# GPS.net
KiCad netlist of a schematic drawn in Altium Designer
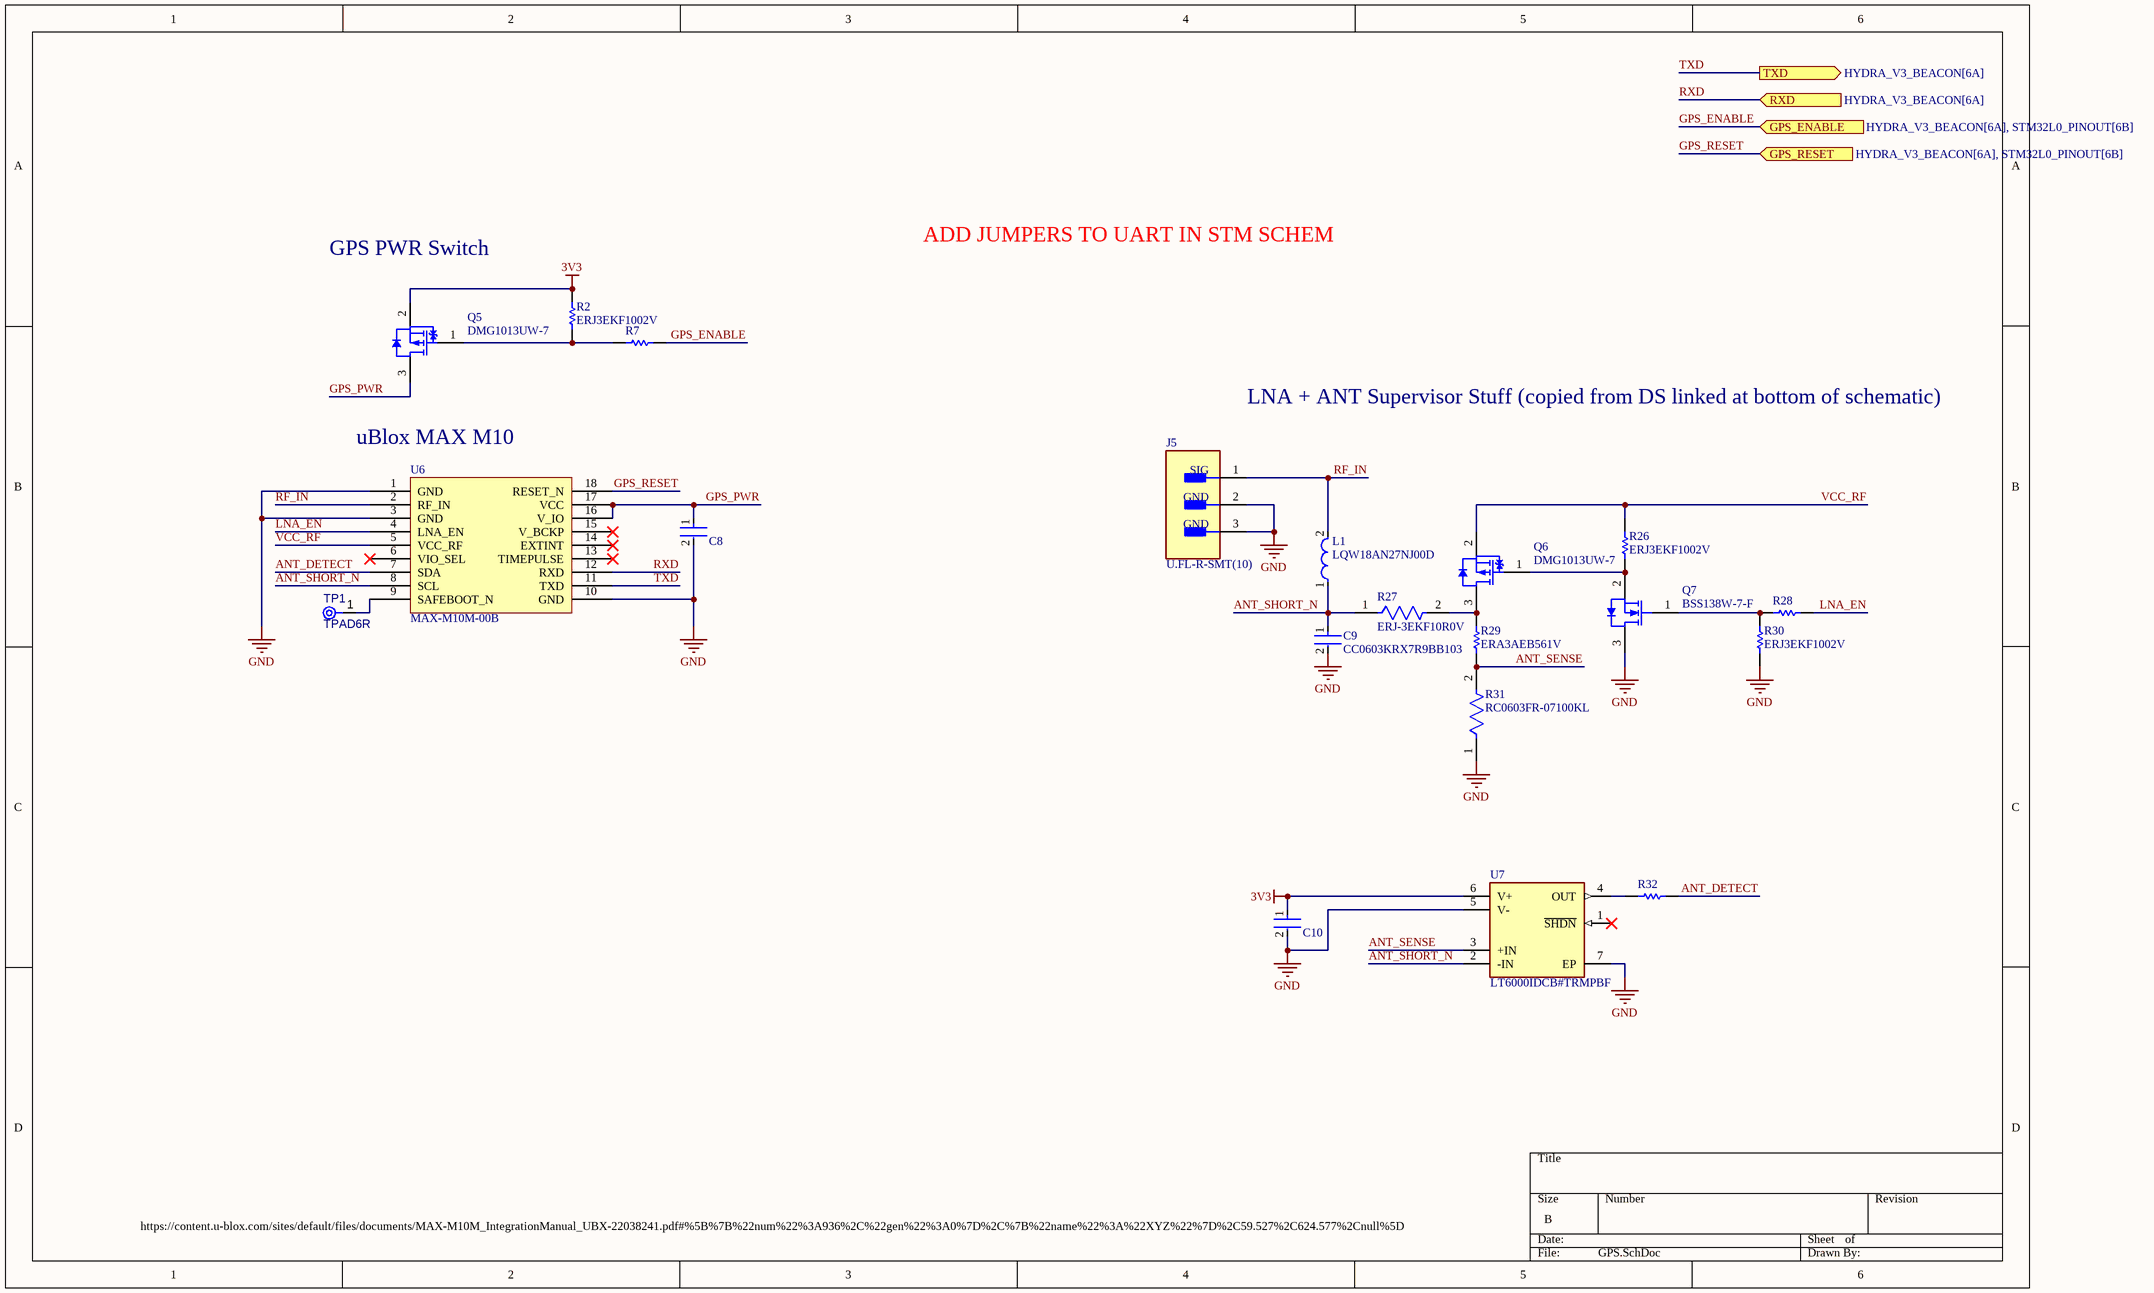
[diagram p0: GPS.SchDoc]

(export (version "E")
  (design (tool "Eeschema 10.0.6"))
  (components
    (comp (ref "C8")
      (value "C0402C104K8PACTU")
      (footprint "FP-C0402-BB-MFG")
      (description "CAP CER 0.1UF 10V X5R 0402")
      (fields (field (name "MANUFACTURER") "Kemet") (field (name "TOLERANCE") "0.1"))
      (libsource (lib "Altium Content Vault") (part "b4654b650e69147ec39a6b967a45e02"))
    )
    (comp (ref "C9")
      (value "CC0603KRX7R9BB103")
      (footprint "FP-CC0603-DA-MFG")
      (description "CAP CER 10000PF 50V X7R 0603")
      (fields (field (name "TOLERANCE") "0.1") (field (name "MANUFACTURER") "YAGEO"))
      (libsource (lib "Altium Content Vault") (part "11868f565c42a9108669ba33697ecf6"))
    )
    (comp (ref "C10")
      (value "C0402C104K8PACTU")
      (footprint "FP-C0402-BB-MFG")
      (description "CAP CER 0.1UF 10V X5R 0402")
      (fields (field (name "MANUFACTURER") "Kemet") (field (name "TOLERANCE") "0.1"))
      (libsource (lib "Altium Content Vault") (part "b4654b650e69147ec39a6b967a45e02"))
    )
    (comp (ref "J5")
      (value "U.FL-R-SMT(10)")
      (footprint "FP-U_FL-R-SMT_10-MFG")
      (description "CONN U.FL RCPT STR 50 OHM SMD")
      (libsource (lib "Altium Content Vault") (part "eef6fde44c591823e8076210edfe12f"))
    )
    (comp (ref "L1")
      (value "LQW18AN27NJ00D")
      (footprint "FP-LQW18AN_00-MFG")
      (description "Wire Wound RF Inductor 27nH ±5% 440mA 0.21Ω 0603 (1608)")
      (fields (field (name "TOLERANCE") "5%"))
      (libsource (lib "Altium Content Vault") (part "725321dda6339637d4d059423bc1c3c"))
    )
    (comp (ref "Q5")
      (value "DMG1013UW-7")
      (footprint "DIOD-SOT323-3_V")
      (fields (field (name "MANUFACTURER") "Diodes Inc"))
      (libsource (lib "Altium Content Vault") (part "PEMOS-GSD-3_C"))
    )
    (comp (ref "Q6")
      (value "DMG1013UW-7")
      (footprint "DIOD-SOT323-3_V")
      (fields (field (name "MANUFACTURER") "Diodes Inc"))
      (libsource (lib "Altium Content Vault") (part "PEMOS-GSD-3_C"))
    )
    (comp (ref "Q7")
      (value "BSS138W-7-F")
      (footprint "DIOD-SOT323-3_V")
      (fields (field (name "MANUFACTURER") "DiodesIncorporated"))
      (libsource (lib "Altium Content Vault") (part "NEMOS-GSD-3"))
    )
    (comp (ref "R2")
      (value "ERJ3EKF1002V")
      (footprint "RESC1609X55X30LL15T15")
      (description "Chip Resistor, 10 KOhm, +/- 1%, 0.1 W, -55 to 155 degC, 0603 (1608 Metric), RoHS, Tape and Reel")
      (fields (field (name "TOLERANCE") "1%") (field (name "MANUFACTURER") "Panasonic"))
      (libsource (lib "Altium Content Vault") (part "RES-2"))
    )
    (comp (ref "R7")
      (value "ERJ-3EKF1001V")
      (footprint "RESC1608X55X30LL15T15")
      (fields (field (name "MANUFACTURER") "Panasonic"))
      (libsource (lib "Altium Content Vault") (part "RES"))
    )
    (comp (ref "R26")
      (value "ERJ3EKF1002V")
      (footprint "RESC1609X55X30LL15T15")
      (description "Chip Resistor, 10 KOhm, +/- 1%, 0.1 W, -55 to 155 degC, 0603 (1608 Metric), RoHS, Tape and Reel")
      (fields (field (name "TOLERANCE") "1%") (field (name "MANUFACTURER") "Panasonic"))
      (libsource (lib "Altium Content Vault") (part "RES-2"))
    )
    (comp (ref "R27")
      (value "ERJ-3EKF10R0V")
      (footprint "FP-ERJ3EK-MFG")
      (description "RES SMD 10 OHM 1% 1/10W 0603")
      (fields
        (field (name "OCTOPART") "https://octopart.com/erj-3ekf10r0v-panasonic-55403649")
        (field (name "MANUFACTURER") "Panasonic")
      )
      (libsource (lib "Altium Content Vault") (part "1029c3af85768c4190bb7ad29bc67b5"))
    )
    (comp (ref "R28")
      (value "ERJ-3EKF1001V")
      (footprint "RESC1608X55X30LL15T15")
      (fields (field (name "MANUFACTURER") "Panasonic"))
      (libsource (lib "Altium Content Vault") (part "RES"))
    )
    (comp (ref "R29")
      (value "ERA3AEB561V")
      (footprint "RESC1608X55X30LL20T20")
      (fields (field (name "MANUFACTURER") "Panasonic"))
      (libsource (lib "Altium Content Vault") (part "RES"))
    )
    (comp (ref "R30")
      (value "ERJ3EKF1002V")
      (footprint "RESC1609X55X30LL15T15")
      (description "Chip Resistor, 10 KOhm, +/- 1%, 0.1 W, -55 to 155 degC, 0603 (1608 Metric), RoHS, Tape and Reel")
      (fields (field (name "TOLERANCE") "1%") (field (name "MANUFACTURER") "Panasonic"))
      (libsource (lib "Altium Content Vault") (part "RES-2"))
    )
    (comp (ref "R31")
      (value "RC0603FR-07100KL")
      (footprint "FP-RC0603-0_55-MFG")
      (description "RES SMD 100K OHM 1% 1/10W 0603")
      (fields (field (name "TOLERANCE") "1%"))
      (libsource (lib "Altium Content Vault") (part "1029c3af85768c4190bb7ad29bc67b5"))
    )
    (comp (ref "R32")
      (value "ERJ-3EKF1001V")
      (footprint "RESC1608X55X30LL15T15")
      (fields (field (name "MANUFACTURER") "Panasonic"))
      (libsource (lib "Altium Content Vault") (part "RES"))
    )
    (comp (ref "TP1")
      (value "TPAD6R")
      (footprint "TP06R")
      (description "0.6mm round")
      (libsource (lib "uORocketry Hardware") (part "CMP-001-0001-4"))
    )
    (comp (ref "U6")
      (value "MAX-M10M-00B")
      (footprint "CAC-110P1035X969-18N")
      (description "Gnss Lcc Rx Mod, Rom, Crystal")
      (libsource (lib "uORocketry Hardware") (part "MAX-M10M-00B"))
    )
    (comp (ref "U7")
      (value "LT6000IDCB#TRMPBF")
      (footprint "FP-DCB-6-05-08-1715-MFG")
      (description "IC OPAMP GP 1 CIRCUIT 6DFN")
      (libsource (lib "Altium Content Vault") (part "33bb285994f2e703f79bf9d86341a8a"))
    )
  )
  (nets
    (net (code "1") (name "/ANT_DETECT") (class "Default")
      (node (ref "R32") (pin "1") (pinfunction "1_1") (pintype "passive"))
      (node (ref "U6") (pin "7") (pinfunction "SDA_7") (pintype "passive"))
    )
    (net (code "2") (name "/ANT_SENSE") (class "Default")
      (node (ref "R29") (pin "1") (pinfunction "1_1") (pintype "passive"))
      (node (ref "R31") (pin "2") (pinfunction "2_2") (pintype "passive"))
      (node (ref "U7") (pin "3") (pinfunction "+IN_3") (pintype "tri_state"))
    )
    (net (code "3") (name "/ANT_SHORT_N") (class "Default")
      (node (ref "C9") (pin "1") (pinfunction "1_1") (pintype "passive"))
      (node (ref "L1") (pin "1") (pinfunction "1_1") (pintype "passive"))
      (node (ref "R27") (pin "1") (pinfunction "1_1") (pintype "passive"))
      (node (ref "U6") (pin "8") (pinfunction "SCL_8") (pintype "passive"))
      (node (ref "U7") (pin "2") (pinfunction "-IN_2") (pintype "tri_state"))
    )
    (net (code "4") (name "/GPS_ENABLE") (class "Default")
      (node (ref "R7") (pin "1") (pinfunction "1_1") (pintype "passive"))
    )
    (net (code "5") (name "/GPS_PWR") (class "Default")
      (node (ref "C8") (pin "1") (pinfunction "1_1") (pintype "passive"))
      (node (ref "Q5") (pin "3") (pinfunction "D_3") (pintype "passive"))
      (node (ref "U6") (pin "16") (pinfunction "V_IO_16") (pintype "passive"))
      (node (ref "U6") (pin "17") (pinfunction "VCC_17") (pintype "passive"))
    )
    (net (code "6") (name "/GPS_RESET") (class "Default")
      (node (ref "U6") (pin "18") (pinfunction "RESET_N_18") (pintype "passive"))
    )
    (net (code "7") (name "/LNA_EN") (class "Default")
      (node (ref "R28") (pin "1") (pinfunction "1_1") (pintype "passive"))
      (node (ref "U6") (pin "4") (pinfunction "LNA_EN_4") (pintype "passive"))
    )
    (net (code "8") (name "/RF_IN") (class "Default")
      (node (ref "J5") (pin "1") (pinfunction "SIG_1") (pintype "passive"))
      (node (ref "L1") (pin "2") (pinfunction "2_2") (pintype "passive"))
      (node (ref "U6") (pin "2") (pinfunction "RF_IN_2") (pintype "passive"))
    )
    (net (code "9") (name "/RXD") (class "Default")
      (node (ref "U6") (pin "12") (pinfunction "RXD_12") (pintype "passive"))
    )
    (net (code "10") (name "/TXD") (class "Default")
      (node (ref "U6") (pin "11") (pinfunction "TXD_11") (pintype "passive"))
    )
    (net (code "11") (name "/VCC_RF") (class "Default")
      (node (ref "Q6") (pin "2") (pinfunction "S_2") (pintype "passive"))
      (node (ref "R26") (pin "2") (pinfunction "2_2") (pintype "passive"))
      (node (ref "U6") (pin "5") (pinfunction "VCC_RF_5") (pintype "passive"))
    )
    (net (code "12") (name "3V3") (class "Default")
      (node (ref "C10") (pin "1") (pinfunction "1_1") (pintype "passive"))
      (node (ref "Q5") (pin "2") (pinfunction "S_2") (pintype "passive"))
      (node (ref "R2") (pin "2") (pinfunction "2_2") (pintype "passive"))
      (node (ref "U7") (pin "6") (pinfunction "V+_6") (pintype "power_in"))
    )
    (net (code "13") (name "GND") (class "Default")
      (node (ref "C10") (pin "2") (pinfunction "2_2") (pintype "passive"))
      (node (ref "C8") (pin "2") (pinfunction "2_2") (pintype "passive"))
      (node (ref "C9") (pin "2") (pinfunction "2_2") (pintype "passive"))
      (node (ref "J5") (pin "2") (pinfunction "GND_2") (pintype "power_in"))
      (node (ref "J5") (pin "3") (pinfunction "GND_3") (pintype "power_in"))
      (node (ref "Q7") (pin "3") (pinfunction "D_3") (pintype "passive"))
      (node (ref "R30") (pin "1") (pinfunction "1_1") (pintype "passive"))
      (node (ref "R31") (pin "1") (pinfunction "1_1") (pintype "passive"))
      (node (ref "U6") (pin "1") (pinfunction "GND_1") (pintype "passive"))
      (node (ref "U6") (pin "10") (pinfunction "GND_10") (pintype "passive"))
      (node (ref "U6") (pin "3") (pinfunction "GND_3") (pintype "passive"))
      (node (ref "U7") (pin "5") (pinfunction "V-_5") (pintype "power_in"))
      (node (ref "U7") (pin "7") (pinfunction "EP_7") (pintype "power_in"))
    )
    (net (code "14") (name "Net-(Q5-G)") (class "Default")
      (node (ref "Q5") (pin "1") (pinfunction "G_1") (pintype "passive"))
      (node (ref "R2") (pin "1") (pinfunction "1_1") (pintype "passive"))
      (node (ref "R7") (pin "2") (pinfunction "2_2") (pintype "passive"))
    )
    (net (code "15") (name "Net-(Q6-D)") (class "Default")
      (node (ref "Q6") (pin "3") (pinfunction "D_3") (pintype "passive"))
      (node (ref "R27") (pin "2") (pinfunction "2_2") (pintype "passive"))
      (node (ref "R29") (pin "2") (pinfunction "2_2") (pintype "passive"))
    )
    (net (code "16") (name "Net-(Q6-G)") (class "Default")
      (node (ref "Q6") (pin "1") (pinfunction "G_1") (pintype "passive"))
      (node (ref "Q7") (pin "2") (pinfunction "S_2") (pintype "passive"))
      (node (ref "R26") (pin "1") (pinfunction "1_1") (pintype "passive"))
    )
    (net (code "17") (name "Net-(Q7-G)") (class "Default")
      (node (ref "Q7") (pin "1") (pinfunction "G_1") (pintype "passive"))
      (node (ref "R28") (pin "2") (pinfunction "2_2") (pintype "passive"))
      (node (ref "R30") (pin "2") (pinfunction "2_2") (pintype "passive"))
    )
    (net (code "18") (name "Net-(TP1-TP)") (class "Default")
      (node (ref "TP1") (pin "1") (pinfunction "TP_1") (pintype "passive"))
      (node (ref "U6") (pin "9") (pinfunction "SAFEBOOT_N_9") (pintype "passive"))
    )
    (net (code "19") (name "Net-(U7-OUT)") (class "Default")
      (node (ref "R32") (pin "2") (pinfunction "2_2") (pintype "passive"))
      (node (ref "U7") (pin "4") (pinfunction "OUT_4") (pintype "output"))
    )
    (net (code "20") (name "unconnected-(U6-EXTINT-Pad14)") (class "Default")
      (node (ref "U6") (pin "14") (pinfunction "EXTINT_14") (pintype "passive+no_connect"))
    )
    (net (code "21") (name "unconnected-(U6-TIMEPULSE-Pad13)") (class "Default")
      (node (ref "U6") (pin "13") (pinfunction "TIMEPULSE_13") (pintype "passive+no_connect"))
    )
    (net (code "22") (name "unconnected-(U6-VIO_SEL-Pad6)") (class "Default")
      (node (ref "U6") (pin "6") (pinfunction "VIO_SEL_6") (pintype "passive+no_connect"))
    )
    (net (code "23") (name "unconnected-(U6-V_BCKP-Pad15)") (class "Default")
      (node (ref "U6") (pin "15") (pinfunction "V_BCKP_15") (pintype "passive+no_connect"))
    )
    (net (code "24") (name "unconnected-(U7-~{SHDN}-Pad1)") (class "Default")
      (node (ref "U7") (pin "1") (pinfunction "~{SHDN}_1") (pintype "input+no_connect"))
    )
  )
)
